# akcel.net
KiCad netlist of a schematic drawn in EAGLE
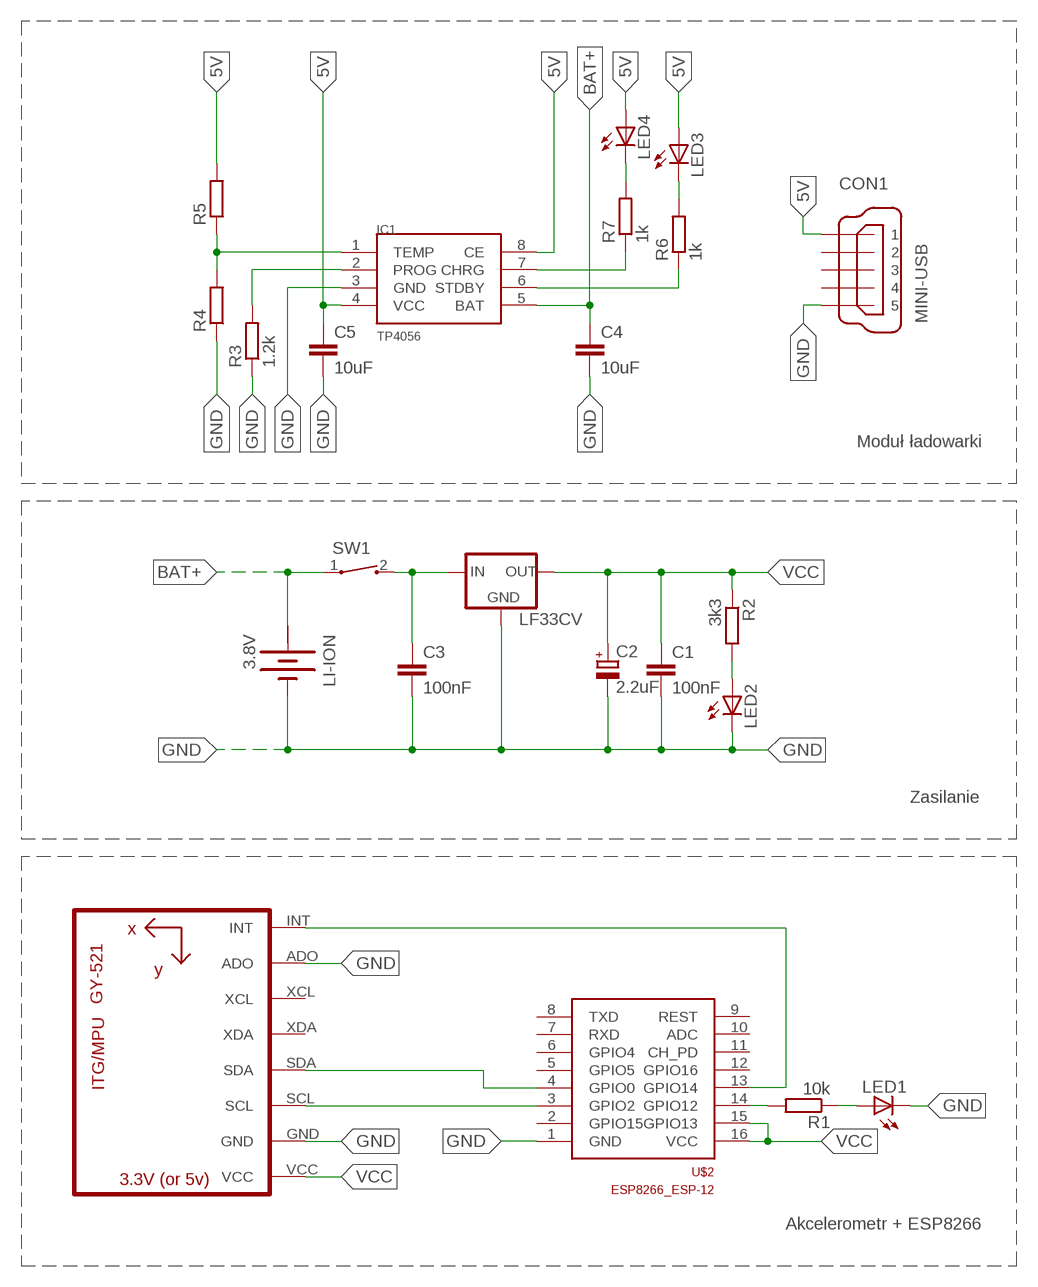
[diagram p0: schematic, sheet 1]

(export (version "E")
  (design (tool "Eeschema 10.0.6"))
  (components
    (comp (ref "C1")
      (value "100nF")
      (footprint "eagle-import:C025-024X044")
      (libsource (lib "eagle-import") (part "C-EU025-024X044"))
    )
    (comp (ref "C2")
      (value "2.2uF")
      (footprint "eagle-import:085CS_1AR")
      (libsource (lib "eagle-import") (part "CPOL-EU085CS-1AR"))
    )
    (comp (ref "C3")
      (value "100nF")
      (footprint "eagle-import:C025-024X044")
      (libsource (lib "eagle-import") (part "C-EU025-024X044"))
    )
    (comp (ref "C4")
      (value "10uF")
      (footprint "eagle-import:C025-024X044")
      (libsource (lib "eagle-import") (part "C-EU025-024X044"))
    )
    (comp (ref "C5")
      (value "10uF")
      (footprint "eagle-import:C025-024X044")
      (libsource (lib "eagle-import") (part "C-EU025-024X044"))
    )
    (comp (ref "CON1")
      (value "MINI-USB")
      (footprint "eagle-import:32005-201")
      (libsource (lib "eagle-import") (part "MINI-USB-32005-201"))
    )
    (comp (ref "IC1")
      (value "TP4056")
      (footprint "eagle-import:SOP-8")
      (libsource (lib "eagle-import") (part "TP4056"))
    )
    (comp (ref "LED1")
      (value "LED10MM")
      (footprint "eagle-import:LED10MM")
      (libsource (lib "eagle-import") (part "LED10MM"))
    )
    (comp (ref "LED2")
      (value "LED10MM")
      (footprint "eagle-import:LED10MM")
      (libsource (lib "eagle-import") (part "LED10MM"))
    )
    (comp (ref "LED3")
      (value "LED10MM")
      (footprint "eagle-import:LED10MM")
      (libsource (lib "eagle-import") (part "LED10MM"))
    )
    (comp (ref "LED4")
      (value "LED10MM")
      (footprint "eagle-import:LED10MM")
      (libsource (lib "eagle-import") (part "LED10MM"))
    )
    (comp (ref "LF33CV")
      (value "LFXXCVS")
      (footprint "eagle-import:TO220S")
      (libsource (lib "eagle-import") (part "LFXXCVS"))
    )
    (comp (ref "LI-ION")
      (value "3.8V")
      (footprint "eagle-import:BATTERY")
      (libsource (lib "eagle-import") (part "BATTERY"))
    )
    (comp (ref "R1")
      (value "10k")
      (footprint "eagle-import:0204V")
      (libsource (lib "eagle-import") (part "R-EU_0204/2V"))
    )
    (comp (ref "R2")
      (value "3k3")
      (footprint "eagle-import:0204V")
      (libsource (lib "eagle-import") (part "R-EU_0204/2V"))
    )
    (comp (ref "R3")
      (value "1.2k")
      (footprint "eagle-import:0204V")
      (libsource (lib "eagle-import") (part "R-EU_0204/2V"))
    )
    (comp (ref "R4")
      (value "R-EU_0204/2V")
      (footprint "eagle-import:0204V")
      (libsource (lib "eagle-import") (part "R-EU_0204/2V"))
    )
    (comp (ref "R5")
      (value "R-EU_0204/2V")
      (footprint "eagle-import:0204V")
      (libsource (lib "eagle-import") (part "R-EU_0204/2V"))
    )
    (comp (ref "R6")
      (value "1k")
      (footprint "eagle-import:0204V")
      (libsource (lib "eagle-import") (part "R-EU_0204/2V"))
    )
    (comp (ref "R7")
      (value "1k")
      (footprint "eagle-import:0204V")
      (libsource (lib "eagle-import") (part "R-EU_0204/2V"))
    )
    (comp (ref "SW1")
      (value "CT10-XXXX-A2")
      (footprint "eagle-import:CT10-XXXX-A2")
      (libsource (lib "eagle-import") (part "CT10-XXXX-A2"))
    )
    (comp (ref "U$2")
      (value "ESP8266_ESP-12")
      (footprint "eagle-import:ESP8266-ESP12")
      (libsource (lib "eagle-import") (part "ESP8266_ESP-12"))
    )
    (comp (ref "U1")
      (value "GY-521MPU6050")
      (footprint "eagle-import:GY-521")
      (libsource (lib "eagle-import") (part "GY-521MPU6050"))
    )
  )
  (nets
    (net (code "1") (name "/+") (class "Default")
      (node (ref "LI-ION") (pin "+@1") (pinfunction "+_+@1") (pintype "power_in"))
    )
    (net (code "2") (name "5V") (class "Default")
      (node (ref "C5") (pin "1") (pinfunction "1_1") (pintype "passive"))
      (node (ref "CON1") (pin "1") (pinfunction "1_1") (pintype "passive"))
      (node (ref "IC1") (pin "4") (pinfunction "VCC_4") (pintype "bidirectional"))
      (node (ref "IC1") (pin "8") (pinfunction "CE_8") (pintype "bidirectional"))
      (node (ref "LED3") (pin "A") (pinfunction "A_A") (pintype "passive"))
      (node (ref "LED4") (pin "A") (pinfunction "A_A") (pintype "passive"))
      (node (ref "R5") (pin "2") (pinfunction "2_2") (pintype "passive"))
    )
    (net (code "3") (name "BAT+") (class "Default")
      (node (ref "C4") (pin "1") (pinfunction "1_1") (pintype "passive"))
      (node (ref "IC1") (pin "5") (pinfunction "BAT_5") (pintype "bidirectional"))
      (node (ref "LI-ION") (pin "+") (pinfunction "+_+") (pintype "power_in"))
      (node (ref "SW1") (pin "1") (pinfunction "1_1") (pintype "passive"))
    )
    (net (code "4") (name "GND") (class "Default")
      (node (ref "C1") (pin "2") (pinfunction "2_2") (pintype "passive"))
      (node (ref "C2") (pin "-") (pinfunction "-_-") (pintype "passive"))
      (node (ref "C3") (pin "2") (pinfunction "2_2") (pintype "passive"))
      (node (ref "C4") (pin "2") (pinfunction "2_2") (pintype "passive"))
      (node (ref "C5") (pin "2") (pinfunction "2_2") (pintype "passive"))
      (node (ref "CON1") (pin "5") (pinfunction "5_5") (pintype "passive"))
      (node (ref "IC1") (pin "3") (pinfunction "GND_3") (pintype "bidirectional"))
      (node (ref "LED1") (pin "K") (pinfunction "C_K") (pintype "passive"))
      (node (ref "LED2") (pin "K") (pinfunction "C_K") (pintype "passive"))
      (node (ref "LF33CV") (pin "2") (pinfunction "GND_2") (pintype "input"))
      (node (ref "LI-ION") (pin "-") (pinfunction "-_-") (pintype "power_in"))
      (node (ref "R3") (pin "1") (pinfunction "1_1") (pintype "passive"))
      (node (ref "R4") (pin "1") (pinfunction "1_1") (pintype "passive"))
      (node (ref "U$2") (pin "1") (pinfunction "GND_1") (pintype "bidirectional"))
      (node (ref "U1") (pin "ADO") (pinfunction "ADO_ADO") (pintype "bidirectional"))
      (node (ref "U1") (pin "GND") (pinfunction "GND_GND") (pintype "bidirectional"))
    )
    (net (code "5") (name "Net-(IC1-CHRG)") (class "Default")
      (node (ref "IC1") (pin "7") (pinfunction "CHRG_7") (pintype "bidirectional"))
      (node (ref "R7") (pin "1") (pinfunction "1_1") (pintype "passive"))
    )
    (net (code "6") (name "Net-(IC1-PROG)") (class "Default")
      (node (ref "IC1") (pin "2") (pinfunction "PROG_2") (pintype "bidirectional"))
      (node (ref "R3") (pin "2") (pinfunction "2_2") (pintype "passive"))
    )
    (net (code "7") (name "Net-(IC1-STDBY)") (class "Default")
      (node (ref "IC1") (pin "6") (pinfunction "STDBY_6") (pintype "bidirectional"))
      (node (ref "R6") (pin "1") (pinfunction "1_1") (pintype "passive"))
    )
    (net (code "8") (name "Net-(IC1-TEMP)") (class "Default")
      (node (ref "IC1") (pin "1") (pinfunction "TEMP_1") (pintype "bidirectional"))
      (node (ref "R4") (pin "2") (pinfunction "2_2") (pintype "passive"))
      (node (ref "R5") (pin "1") (pinfunction "1_1") (pintype "passive"))
    )
    (net (code "9") (name "Net-(LED1-PadA)") (class "Default")
      (node (ref "LED1") (pin "A") (pinfunction "A_A") (pintype "passive"))
      (node (ref "R1") (pin "1") (pinfunction "1_1") (pintype "passive"))
    )
    (net (code "10") (name "Net-(LED2-PadA)") (class "Default")
      (node (ref "LED2") (pin "A") (pinfunction "A_A") (pintype "passive"))
      (node (ref "R2") (pin "2") (pinfunction "2_2") (pintype "passive"))
    )
    (net (code "11") (name "Net-(LED3-C)") (class "Default")
      (node (ref "LED3") (pin "K") (pinfunction "C_K") (pintype "passive"))
      (node (ref "R6") (pin "2") (pinfunction "2_2") (pintype "passive"))
    )
    (net (code "12") (name "Net-(LED4-C)") (class "Default")
      (node (ref "LED4") (pin "K") (pinfunction "C_K") (pintype "passive"))
      (node (ref "R7") (pin "2") (pinfunction "2_2") (pintype "passive"))
    )
    (net (code "13") (name "Net-(LF33CV-IN)") (class "Default")
      (node (ref "C3") (pin "1") (pinfunction "1_1") (pintype "passive"))
      (node (ref "LF33CV") (pin "1") (pinfunction "IN_1") (pintype "input"))
      (node (ref "SW1") (pin "2") (pinfunction "2_2") (pintype "passive"))
    )
    (net (code "14") (name "Net-(U$2-GPIO0)") (class "Default")
      (node (ref "U$2") (pin "4") (pinfunction "GPIO0_4") (pintype "bidirectional"))
      (node (ref "U1") (pin "SDA") (pinfunction "SDA_SDA") (pintype "bidirectional"))
    )
    (net (code "15") (name "Net-(U$2-GPIO2)") (class "Default")
      (node (ref "U$2") (pin "3") (pinfunction "GPIO2_3") (pintype "bidirectional"))
      (node (ref "U1") (pin "SCL") (pinfunction "SCL_SCL") (pintype "bidirectional"))
    )
    (net (code "16") (name "Net-(U$2-GPIO12)") (class "Default")
      (node (ref "R1") (pin "2") (pinfunction "2_2") (pintype "passive"))
      (node (ref "U$2") (pin "14") (pinfunction "GPIO12_14") (pintype "bidirectional"))
    )
    (net (code "17") (name "Net-(U$2-GPIO14)") (class "Default")
      (node (ref "U$2") (pin "13") (pinfunction "GPIO14_13") (pintype "bidirectional"))
      (node (ref "U1") (pin "INT") (pinfunction "INT_INT") (pintype "bidirectional"))
    )
    (net (code "18") (name "VCC") (class "Default")
      (node (ref "C1") (pin "1") (pinfunction "1_1") (pintype "passive"))
      (node (ref "C2") (pin "+") (pinfunction "+_+") (pintype "passive"))
      (node (ref "LF33CV") (pin "3") (pinfunction "OUT_3") (pintype "passive"))
      (node (ref "R2") (pin "1") (pinfunction "1_1") (pintype "passive"))
      (node (ref "U$2") (pin "15") (pinfunction "GPIO13_15") (pintype "bidirectional"))
      (node (ref "U$2") (pin "16") (pinfunction "VCC_16") (pintype "bidirectional"))
      (node (ref "U1") (pin "VCC") (pinfunction "VCC_VCC") (pintype "bidirectional"))
    )
    (net (code "19") (name "unconnected-(CON1-Pad2)") (class "Default")
      (node (ref "CON1") (pin "2") (pinfunction "2_2") (pintype "passive"))
    )
    (net (code "20") (name "unconnected-(CON1-Pad3)") (class "Default")
      (node (ref "CON1") (pin "3") (pinfunction "3_3") (pintype "passive"))
    )
    (net (code "21") (name "unconnected-(CON1-Pad4)") (class "Default")
      (node (ref "CON1") (pin "4") (pinfunction "4_4") (pintype "passive"))
    )
    (net (code "22") (name "unconnected-(U$2-ADC-Pad10)") (class "Default")
      (node (ref "U$2") (pin "10") (pinfunction "ADC_10") (pintype "bidirectional"))
    )
    (net (code "23") (name "unconnected-(U$2-CH_PD-Pad11)") (class "Default")
      (node (ref "U$2") (pin "11") (pinfunction "CH_PD_11") (pintype "bidirectional"))
    )
    (net (code "24") (name "unconnected-(U$2-GPIO4-Pad6)") (class "Default")
      (node (ref "U$2") (pin "6") (pinfunction "GPIO4_6") (pintype "bidirectional"))
    )
    (net (code "25") (name "unconnected-(U$2-GPIO5-Pad5)") (class "Default")
      (node (ref "U$2") (pin "5") (pinfunction "GPIO5_5") (pintype "bidirectional"))
    )
    (net (code "26") (name "unconnected-(U$2-GPIO15-Pad2)") (class "Default")
      (node (ref "U$2") (pin "2") (pinfunction "GPIO15_2") (pintype "bidirectional"))
    )
    (net (code "27") (name "unconnected-(U$2-GPIO16-Pad12)") (class "Default")
      (node (ref "U$2") (pin "12") (pinfunction "GPIO16_12") (pintype "bidirectional"))
    )
    (net (code "28") (name "unconnected-(U$2-REST-Pad9)") (class "Default")
      (node (ref "U$2") (pin "9") (pinfunction "REST_9") (pintype "bidirectional"))
    )
    (net (code "29") (name "unconnected-(U$2-RXD-Pad7)") (class "Default")
      (node (ref "U$2") (pin "7") (pinfunction "RXD_7") (pintype "bidirectional"))
    )
    (net (code "30") (name "unconnected-(U$2-TXD-Pad8)") (class "Default")
      (node (ref "U$2") (pin "8") (pinfunction "TXD_8") (pintype "bidirectional"))
    )
    (net (code "31") (name "unconnected-(U1-PadXCL)") (class "Default")
      (node (ref "U1") (pin "XCL") (pinfunction "XCL_XCL") (pintype "bidirectional"))
    )
    (net (code "32") (name "unconnected-(U1-PadXDA)") (class "Default")
      (node (ref "U1") (pin "XDA") (pinfunction "XDA_XDA") (pintype "bidirectional"))
    )
  )
)
